# 02_-_Power_CSI_and_Bank_Power.net
KiCad netlist of a schematic drawn in Altium Designer
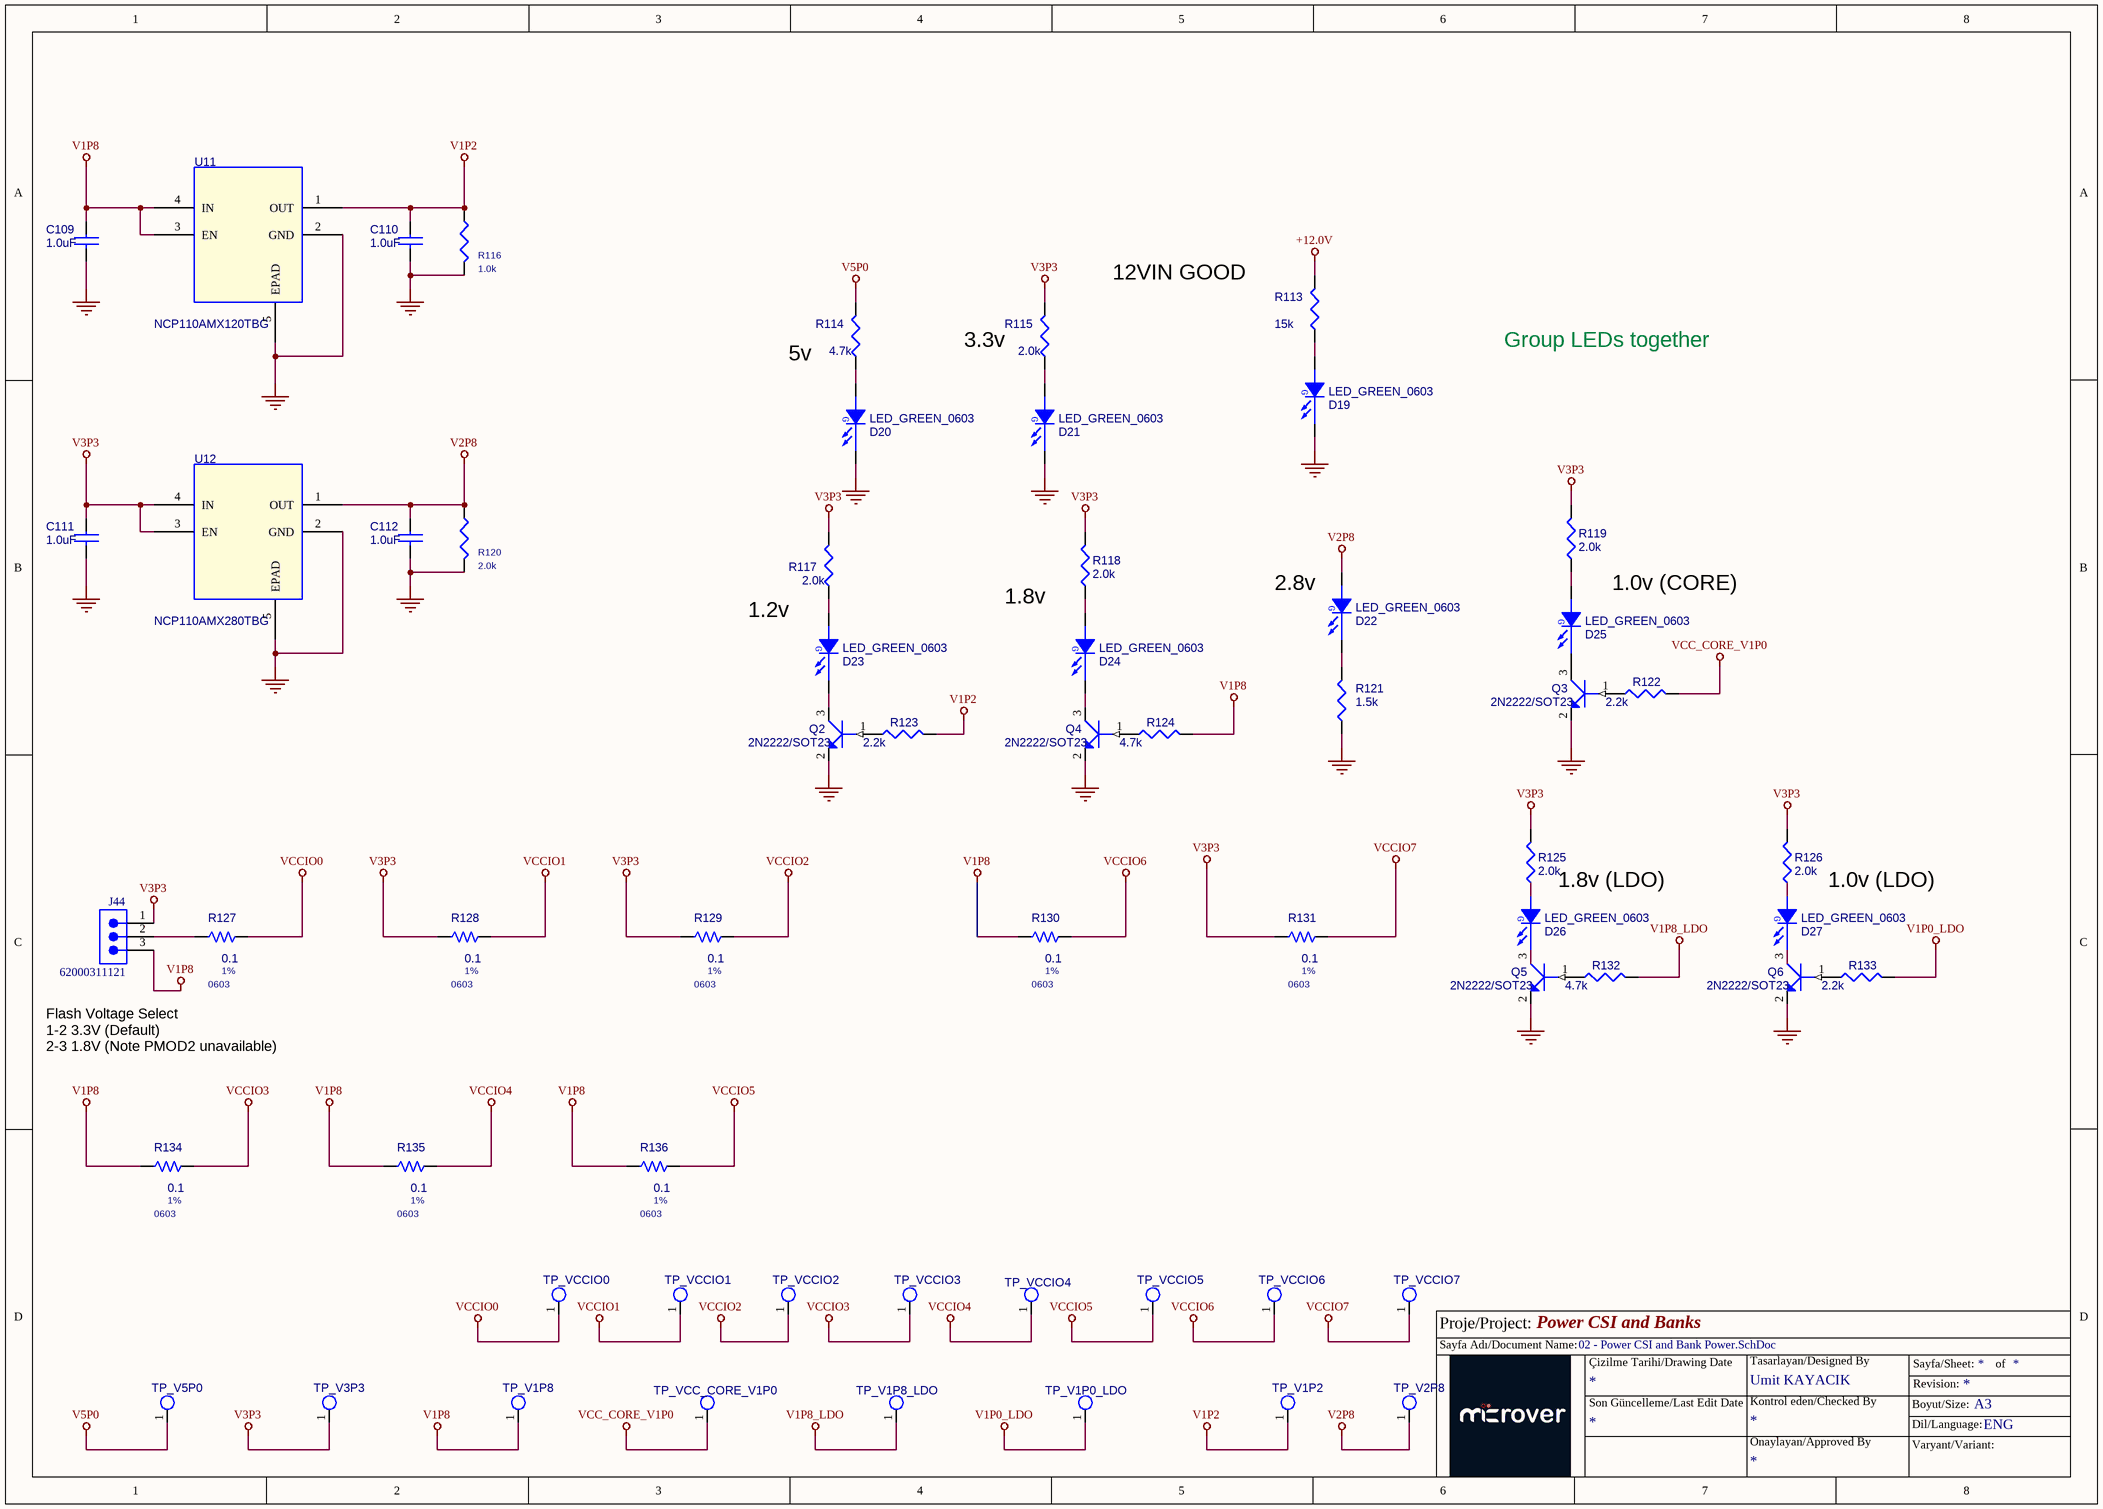
[diagram p0: 02 - Power CSI and Bank Power.SchDoc]

(export (version "E")
  (design (tool "Eeschema 10.0.6"))
  (components
    (comp (ref "C109")
      (value "1.0uF")
      (footprint "C0603")
      (description "CAP CER 10UF 10V 20% X6S 0603")
      (fields
        (field (name "MANUFACTURER PART NUMBER") "CL10X106MP8NRNC")
        (field (name "MANUFACTURER") "Samsung")
      )
      (libsource (lib "*") (part "CAP NP"))
    )
    (comp (ref "C110")
      (value "1.0uF")
      (footprint "C0603")
      (description "CAP CER 10UF 10V 20% X6S 0603")
      (fields
        (field (name "MANUFACTURER PART NUMBER") "CL10X106MP8NRNC")
        (field (name "MANUFACTURER") "Samsung")
      )
      (libsource (lib "*") (part "CAP NP"))
    )
    (comp (ref "C111")
      (value "1.0uF")
      (footprint "C0603")
      (description "CAP CER 10UF 10V 20% X6S 0603")
      (fields (field (name "MFG") "Samsung") (field (name "MAN. PART #") "CL10X106MP8NRNC"))
      (libsource (lib "*") (part "CAP NP"))
    )
    (comp (ref "C112")
      (value "1.0uF")
      (footprint "C0603")
      (description "CAP CER 10UF 10V 20% X6S 0603")
      (fields (field (name "MFG") "Samsung") (field (name "MAN. PART #") "CL10X106MP8NRNC"))
      (libsource (lib "*") (part "CAP NP"))
    )
    (comp (ref "D19")
      (value "LED_GREEN_0603")
      (footprint "APT1608")
      (libsource (lib "*") (part "LED-SMT1206_GREEN_1"))
    )
    (comp (ref "D20")
      (value "LED_GREEN_0603")
      (footprint "APT1608")
      (libsource (lib "*") (part "LED-SMT1206_GREEN_1"))
    )
    (comp (ref "D21")
      (value "LED_GREEN_0603")
      (footprint "APT1608")
      (libsource (lib "*") (part "LED-SMT1206_GREEN_1"))
    )
    (comp (ref "D22")
      (value "LED_GREEN_0603")
      (footprint "APT1608")
      (libsource (lib "*") (part "LED-SMT1206_GREEN_1"))
    )
    (comp (ref "D23")
      (value "LED_GREEN_0603")
      (footprint "APT1608")
      (libsource (lib "*") (part "LED-SMT1206_GREEN_1"))
    )
    (comp (ref "D24")
      (value "LED_GREEN_0603")
      (footprint "APT1608")
      (libsource (lib "*") (part "LED-SMT1206_GREEN_1"))
    )
    (comp (ref "D25")
      (value "LED_GREEN_0603")
      (footprint "APT1608")
      (libsource (lib "*") (part "LED-SMT1206_GREEN_1"))
    )
    (comp (ref "D26")
      (value "LED_GREEN_0603")
      (footprint "APT1608")
      (libsource (lib "*") (part "LED-SMT1206_GREEN_1"))
    )
    (comp (ref "D27")
      (value "LED_GREEN_0603")
      (footprint "APT1608")
      (libsource (lib "*") (part "LED-SMT1206_GREEN_1"))
    )
    (comp (ref "J44")
      (value "62000311121")
      (footprint "62000311121")
      (description "THT Vertical Pin Header WR-PHD, Pitch 2.00 mm, Single Row, 3 pins")
      (libsource (lib "Altium Content Vault") (part "Header_Male_1R_03P"))
    )
    (comp (ref "Q2") (value "2N2222/SOT23") (footprint "MMBT2222ALT-1") (libsource (lib "*") (part "2N2222")))
    (comp (ref "Q3") (value "2N2222/SOT23") (footprint "MMBT2222ALT-1") (libsource (lib "*") (part "2N2222")))
    (comp (ref "Q4") (value "2N2222/SOT23") (footprint "MMBT2222ALT-1") (libsource (lib "*") (part "2N2222")))
    (comp (ref "Q5") (value "2N2222/SOT23") (footprint "MMBT2222ALT-1") (libsource (lib "*") (part "2N2222")))
    (comp (ref "Q6") (value "2N2222/SOT23") (footprint "MMBT2222ALT-1") (libsource (lib "*") (part "2N2222")))
    (comp (ref "R113") (value "15k") (footprint "RLP-103") (libsource (lib "*") (part "RES_0")))
    (comp (ref "R114")
      (value "4.7k")
      (footprint "R0402")
      (description "RES SMD 2.2K OHM 1% 1/10W 0402")
      (fields
        (field (name "MANUFACTURER PART NUMBER") "ERJ-2RKF2201X")
        (field (name "MANUFACTURER") "Panasonic")
      )
      (libsource (lib "*") (part "RES_0"))
    )
    (comp (ref "R115")
      (value "2.0k")
      (footprint "R0402")
      (description "RES SMD 1K OHM 1% 1/10W 0402")
      (fields
        (field (name "MANUFACTURER") "Panasonic")
        (field (name "MANUFACTURER PART NUMBER") "ERJ-2RKF1001X")
      )
      (libsource (lib "*") (part "RES_0"))
    )
    (comp (ref "R116")
      (value "1.0k")
      (footprint "R0402")
      (description "RES SMD 1K OHM 1% 1/10W 0402")
      (fields (field (name "MFG") "Stackpole Electronics Inc") (field (name "MANUFACTURER") "Panasonic"))
      (libsource (lib "*") (part "RES_1K_1W16_0402_5P"))
    )
    (comp (ref "R117")
      (value "2.0k")
      (footprint "R0402")
      (description "RES SMD 1K OHM 1% 1/10W 0402")
      (fields
        (field (name "MANUFACTURER PART NUMBER") "ERJ-2RKF1001X")
        (field (name "MANUFACTURER") "Panasonic")
      )
      (libsource (lib "*") (part "RES_0"))
    )
    (comp (ref "R118")
      (value "2.0k")
      (footprint "R0402")
      (description "RES SMD 1K OHM 1% 1/10W 0402")
      (fields
        (field (name "MANUFACTURER PART NUMBER") "ERJ-2RKF1001X")
        (field (name "MANUFACTURER") "Panasonic")
      )
      (libsource (lib "*") (part "RES_0"))
    )
    (comp (ref "R119")
      (value "2.0k")
      (footprint "R0402")
      (description "RES SMD 1K OHM 1% 1/10W 0402")
      (fields
        (field (name "MANUFACTURER PART NUMBER") "ERJ-2RKF1001X")
        (field (name "MANUFACTURER") "Panasonic")
      )
      (libsource (lib "*") (part "RES_0"))
    )
    (comp (ref "R120")
      (value "2.0k")
      (footprint "R0402")
      (description "RES SMD 1K OHM 1% 1/10W 0402")
      (fields
        (field (name "MFG") "Stackpole Electronics Inc")
        (field (name "MANUFACTURER PART NUMBER") "ERJ-2RKF1001X")
      )
      (libsource (lib "*") (part "RES_1K_1W16_0402_5P"))
    )
    (comp (ref "R121")
      (value "1.5k")
      (footprint "R0402")
      (description "RES SMD 750 OHM 5% 1/10W 0402")
      (fields
        (field (name "MANUFACTURER") "Panasonic")
        (field (name "MANUFACTURER PART NUMBER") "ERJ-2GEJ751X")
      )
      (libsource (lib "*") (part "RES_0"))
    )
    (comp (ref "R122")
      (value "2.2k")
      (footprint "R0402")
      (description "RES SMD 4.7K OHM 5% 1/10W 0402")
      (fields
        (field (name "MANUFACTURER") "Panasonic")
        (field (name "MANUFACTURER PART NUMBER") "ERJ-2GEJ472X")
      )
      (libsource (lib "*") (part "RES_0"))
    )
    (comp (ref "R123")
      (value "2.2k")
      (footprint "R0402")
      (description "RES SMD 4.7K OHM 5% 1/10W 0402")
      (fields
        (field (name "MANUFACTURER") "Panasonic")
        (field (name "MANUFACTURER PART NUMBER") "ERJ-2GEJ472X")
      )
      (libsource (lib "*") (part "RES_0"))
    )
    (comp (ref "R124")
      (value "4.7k")
      (footprint "R0402")
      (description "RES SMD 4.7K OHM 5% 1/10W 0402")
      (fields
        (field (name "MANUFACTURER") "Panasonic")
        (field (name "MANUFACTURER PART NUMBER") "ERJ-2GEJ472X")
      )
      (libsource (lib "*") (part "RES_0"))
    )
    (comp (ref "R125")
      (value "2.0k")
      (footprint "R0402")
      (description "RES SMD 1K OHM 1% 1/10W 0402")
      (fields
        (field (name "MANUFACTURER") "Panasonic")
        (field (name "MANUFACTURER PART NUMBER") "ERJ-2RKF1001X")
      )
      (libsource (lib "*") (part "RES_0"))
    )
    (comp (ref "R126")
      (value "2.0k")
      (footprint "R0402")
      (description "RES SMD 1K OHM 1% 1/10W 0402")
      (fields
        (field (name "MANUFACTURER PART NUMBER") "ERJ-2RKF1001X")
        (field (name "MANUFACTURER") "Panasonic")
      )
      (libsource (lib "*") (part "RES_0"))
    )
    (comp (ref "R127")
      (value "0.1")
      (footprint "0603")
      (fields
        (field (name "VOLTAGE") "RVMAX")
        (field (name "POWER") "RMAX")
        (field (name "TOLLERANCE") "1%")
        (field (name "PCB FOOTPRINT") "0603")
      )
      (libsource (lib "*") (part "R_Dup2"))
    )
    (comp (ref "R128")
      (value "0.1")
      (footprint "0603")
      (fields
        (field (name "VOLTAGE") "RVMAX")
        (field (name "POWER") "RMAX")
        (field (name "TOLLERANCE") "1%")
        (field (name "PCB FOOTPRINT") "0603")
      )
      (libsource (lib "*") (part "R_Dup2"))
    )
    (comp (ref "R129")
      (value "0.1")
      (footprint "0603")
      (fields
        (field (name "VOLTAGE") "RVMAX")
        (field (name "POWER") "RMAX")
        (field (name "TOLLERANCE") "1%")
        (field (name "PCB FOOTPRINT") "0603")
      )
      (libsource (lib "*") (part "R_Dup2"))
    )
    (comp (ref "R130")
      (value "0.1")
      (footprint "0603")
      (fields
        (field (name "VOLTAGE") "RVMAX")
        (field (name "POWER") "RMAX")
        (field (name "TOLLERANCE") "1%")
        (field (name "PCB FOOTPRINT") "0603")
      )
      (libsource (lib "*") (part "R_Dup2"))
    )
    (comp (ref "R131")
      (value "0.1")
      (footprint "0603")
      (fields
        (field (name "VOLTAGE") "RVMAX")
        (field (name "POWER") "RMAX")
        (field (name "TOLLERANCE") "1%")
        (field (name "PCB FOOTPRINT") "0603")
      )
      (libsource (lib "*") (part "R_Dup2"))
    )
    (comp (ref "R132")
      (value "4.7k")
      (footprint "R0402")
      (description "RES SMD 4.7K OHM 5% 1/10W 0402")
      (fields (field (name "MANUFACTURER PART NUMBER") "ERJ-2GEJ472X") (field (name "MFG") "Panasonic"))
      (libsource (lib "*") (part "RES_0"))
    )
    (comp (ref "R133")
      (value "2.2k")
      (footprint "R0402")
      (description "RES SMD 4.7K OHM 5% 1/10W 0402")
      (fields (field (name "MANUFACTURER PART NUMBER") "ERJ-2GEJ472X") (field (name "MFG") "Panasonic"))
      (libsource (lib "*") (part "RES_0"))
    )
    (comp (ref "R134")
      (value "0.1")
      (footprint "0603")
      (fields
        (field (name "VOLTAGE") "RVMAX")
        (field (name "POWER") "RMAX")
        (field (name "TOLLERANCE") "1%")
        (field (name "PCB FOOTPRINT") "0603")
      )
      (libsource (lib "*") (part "R_Dup2"))
    )
    (comp (ref "R135")
      (value "0.1")
      (footprint "0603")
      (fields
        (field (name "VOLTAGE") "RVMAX")
        (field (name "POWER") "RMAX")
        (field (name "TOLLERANCE") "1%")
        (field (name "PCB FOOTPRINT") "0603")
      )
      (libsource (lib "*") (part "R_Dup2"))
    )
    (comp (ref "R136")
      (value "0.1")
      (footprint "0603")
      (fields
        (field (name "VOLTAGE") "RVMAX")
        (field (name "POWER") "RMAX")
        (field (name "TOLLERANCE") "1%")
        (field (name "PCB FOOTPRINT") "0603")
      )
      (libsource (lib "*") (part "R_Dup2"))
    )
    (comp (ref "TP_V1P0_LDO")
      (value "TP_S_40_63")
      (footprint "TP_1MM")
      (description "Square test point, 40mil inner diameter, 63mil outer diameter")
      (libsource (lib "*") (part "TP_S_40_63"))
    )
    (comp (ref "TP_V1P2")
      (value "TP_S_40_63")
      (footprint "TP_1MM")
      (description "Square test point, 40mil inner diameter, 63mil outer diameter")
      (libsource (lib "*") (part "TP_S_40_63"))
    )
    (comp (ref "TP_V1P8")
      (value "TP_S_40_63")
      (footprint "TP_1MM")
      (description "Square test point, 40mil inner diameter, 63mil outer diameter")
      (libsource (lib "*") (part "TP_S_40_63"))
    )
    (comp (ref "TP_V1P8_LDO")
      (value "TP_S_40_63")
      (footprint "TP_1MM")
      (description "Square test point, 40mil inner diameter, 63mil outer diameter")
      (libsource (lib "*") (part "TP_S_40_63"))
    )
    (comp (ref "TP_V2P8")
      (value "TP_S_40_63")
      (footprint "TP_1MM")
      (description "Square test point, 40mil inner diameter, 63mil outer diameter")
      (libsource (lib "*") (part "TP_S_40_63"))
    )
    (comp (ref "TP_V3P3")
      (value "TP_S_40_63")
      (footprint "TP_1MM")
      (description "Square test point, 40mil inner diameter, 63mil outer diameter")
      (libsource (lib "*") (part "TP_S_40_63"))
    )
    (comp (ref "TP_V5P0")
      (value "TP_S_40_63")
      (footprint "TP_1MM")
      (description "Square test point, 40mil inner diameter, 63mil outer diameter")
      (libsource (lib "*") (part "TP_S_40_63"))
    )
    (comp (ref "TP_VCCIO0")
      (value "TP_S_40_63")
      (footprint "TP_1MM")
      (description "Square test point, 40mil inner diameter, 63mil outer diameter")
      (libsource (lib "*") (part "TP_S_40_63"))
    )
    (comp (ref "TP_VCCIO1")
      (value "TP_S_40_63")
      (footprint "TP_1MM")
      (description "Square test point, 40mil inner diameter, 63mil outer diameter")
      (libsource (lib "*") (part "TP_S_40_63"))
    )
    (comp (ref "TP_VCCIO2")
      (value "TP_S_40_63")
      (footprint "TP_1MM")
      (description "Square test point, 40mil inner diameter, 63mil outer diameter")
      (libsource (lib "*") (part "TP_S_40_63"))
    )
    (comp (ref "TP_VCCIO3")
      (value "TP_S_40_63")
      (footprint "TP_1MM")
      (description "Square test point, 40mil inner diameter, 63mil outer diameter")
      (libsource (lib "*") (part "TP_S_40_63"))
    )
    (comp (ref "TP_VCCIO4")
      (value "TP_S_40_63")
      (footprint "TP_1MM")
      (description "Square test point, 40mil inner diameter, 63mil outer diameter")
      (libsource (lib "*") (part "TP_S_40_63"))
    )
    (comp (ref "TP_VCCIO5")
      (value "TP_S_40_63")
      (footprint "TP_1MM")
      (description "Square test point, 40mil inner diameter, 63mil outer diameter")
      (libsource (lib "*") (part "TP_S_40_63"))
    )
    (comp (ref "TP_VCCIO6")
      (value "TP_S_40_63")
      (footprint "TP_1MM")
      (description "Square test point, 40mil inner diameter, 63mil outer diameter")
      (libsource (lib "*") (part "TP_S_40_63"))
    )
    (comp (ref "TP_VCCIO7")
      (value "TP_S_40_63")
      (footprint "TP_1MM")
      (description "Square test point, 40mil inner diameter, 63mil outer diameter")
      (libsource (lib "*") (part "TP_S_40_63"))
    )
    (comp (ref "TP_VCC_CORE_V1P0")
      (value "TP_S_40_63")
      (footprint "TP_1MM")
      (description "Square test point, 40mil inner diameter, 63mil outer diameter")
      (libsource (lib "*") (part "TP_S_40_63"))
    )
    (comp (ref "U11")
      (value "NCP110AMX120TBG")
      (footprint "4XDFN_NCP110")
      (libsource (lib "*") (part "NCP110AMX120TBG"))
    )
    (comp (ref "U12")
      (value "NCP110AMX280TBG")
      (footprint "4XDFN_NCP110")
      (libsource (lib "*") (part "NCP110AMX280TBG"))
    )
  )
  (nets
    (net (code "1") (name "+12.0V") (class "Default")
      (node (ref "R113") (pin "2") (pinfunction "2_2") (pintype "passive"))
    )
    (net (code "2") (name "GND") (class "Default")
      (node (ref "C109") (pin "2") (pinfunction "2_2") (pintype "passive"))
      (node (ref "C110") (pin "2") (pinfunction "2_2") (pintype "passive"))
      (node (ref "C111") (pin "2") (pinfunction "2_2") (pintype "passive"))
      (node (ref "C112") (pin "2") (pinfunction "2_2") (pintype "passive"))
      (node (ref "D19") (pin "1") (pinfunction "CATHODE_1") (pintype "passive"))
      (node (ref "D20") (pin "1") (pinfunction "CATHODE_1") (pintype "passive"))
      (node (ref "D21") (pin "1") (pinfunction "CATHODE_1") (pintype "passive"))
      (node (ref "Q2") (pin "2") (pinfunction "EMITTER_2") (pintype "passive"))
      (node (ref "Q3") (pin "2") (pinfunction "EMITTER_2") (pintype "passive"))
      (node (ref "Q4") (pin "2") (pinfunction "EMITTER_2") (pintype "passive"))
      (node (ref "Q5") (pin "2") (pinfunction "EMITTER_2") (pintype "passive"))
      (node (ref "Q6") (pin "2") (pinfunction "EMITTER_2") (pintype "passive"))
      (node (ref "R116") (pin "2") (pinfunction "2_2") (pintype "passive"))
      (node (ref "R120") (pin "2") (pinfunction "2_2") (pintype "passive"))
      (node (ref "R121") (pin "1") (pinfunction "1_1") (pintype "passive"))
      (node (ref "U11") (pin "2") (pinfunction "GND_2") (pintype "passive"))
      (node (ref "U11") (pin "5") (pinfunction "EPAD_5") (pintype "passive"))
      (node (ref "U12") (pin "2") (pinfunction "GND_2") (pintype "passive"))
      (node (ref "U12") (pin "5") (pinfunction "EPAD_5") (pintype "passive"))
    )
    (net (code "3") (name "Net-(D19-ANODE)") (class "Default")
      (node (ref "D19") (pin "2") (pinfunction "ANODE_2") (pintype "passive"))
      (node (ref "R113") (pin "1") (pinfunction "1_1") (pintype "passive"))
    )
    (net (code "4") (name "Net-(D20-ANODE)") (class "Default")
      (node (ref "D20") (pin "2") (pinfunction "ANODE_2") (pintype "passive"))
      (node (ref "R114") (pin "1") (pinfunction "1_1") (pintype "passive"))
    )
    (net (code "5") (name "Net-(D21-ANODE)") (class "Default")
      (node (ref "D21") (pin "2") (pinfunction "ANODE_2") (pintype "passive"))
      (node (ref "R115") (pin "1") (pinfunction "1_1") (pintype "passive"))
    )
    (net (code "6") (name "Net-(D22-CATHODE)") (class "Default")
      (node (ref "D22") (pin "1") (pinfunction "CATHODE_1") (pintype "passive"))
      (node (ref "R121") (pin "2") (pinfunction "2_2") (pintype "passive"))
    )
    (net (code "7") (name "Net-(D23-ANODE)") (class "Default")
      (node (ref "D23") (pin "2") (pinfunction "ANODE_2") (pintype "passive"))
      (node (ref "R117") (pin "1") (pinfunction "1_1") (pintype "passive"))
    )
    (net (code "8") (name "Net-(D23-CATHODE)") (class "Default")
      (node (ref "D23") (pin "1") (pinfunction "CATHODE_1") (pintype "passive"))
      (node (ref "Q2") (pin "3") (pinfunction "COLLECTOR_3") (pintype "passive"))
    )
    (net (code "9") (name "Net-(D24-ANODE)") (class "Default")
      (node (ref "D24") (pin "2") (pinfunction "ANODE_2") (pintype "passive"))
      (node (ref "R118") (pin "1") (pinfunction "1_1") (pintype "passive"))
    )
    (net (code "10") (name "Net-(D24-CATHODE)") (class "Default")
      (node (ref "D24") (pin "1") (pinfunction "CATHODE_1") (pintype "passive"))
      (node (ref "Q4") (pin "3") (pinfunction "COLLECTOR_3") (pintype "passive"))
    )
    (net (code "11") (name "Net-(D25-ANODE)") (class "Default")
      (node (ref "D25") (pin "2") (pinfunction "ANODE_2") (pintype "passive"))
      (node (ref "R119") (pin "1") (pinfunction "1_1") (pintype "passive"))
    )
    (net (code "12") (name "Net-(D25-CATHODE)") (class "Default")
      (node (ref "D25") (pin "1") (pinfunction "CATHODE_1") (pintype "passive"))
      (node (ref "Q3") (pin "3") (pinfunction "COLLECTOR_3") (pintype "passive"))
    )
    (net (code "13") (name "Net-(D26-ANODE)") (class "Default")
      (node (ref "D26") (pin "2") (pinfunction "ANODE_2") (pintype "passive"))
      (node (ref "R125") (pin "1") (pinfunction "1_1") (pintype "passive"))
    )
    (net (code "14") (name "Net-(D26-CATHODE)") (class "Default")
      (node (ref "D26") (pin "1") (pinfunction "CATHODE_1") (pintype "passive"))
      (node (ref "Q5") (pin "3") (pinfunction "COLLECTOR_3") (pintype "passive"))
    )
    (net (code "15") (name "Net-(D27-ANODE)") (class "Default")
      (node (ref "D27") (pin "2") (pinfunction "ANODE_2") (pintype "passive"))
      (node (ref "R126") (pin "1") (pinfunction "1_1") (pintype "passive"))
    )
    (net (code "16") (name "Net-(D27-CATHODE)") (class "Default")
      (node (ref "D27") (pin "1") (pinfunction "CATHODE_1") (pintype "passive"))
      (node (ref "Q6") (pin "3") (pinfunction "COLLECTOR_3") (pintype "passive"))
    )
    (net (code "17") (name "Net-(J44-Pad2)") (class "Default")
      (node (ref "J44") (pin "2") (pinfunction "2_2") (pintype "passive"))
      (node (ref "R127") (pin "1") (pinfunction "1_1") (pintype "passive"))
    )
    (net (code "18") (name "Net-(Q2-BASE)") (class "Default")
      (node (ref "Q2") (pin "1") (pinfunction "BASE_1") (pintype "input"))
      (node (ref "R123") (pin "1") (pinfunction "1_1") (pintype "passive"))
    )
    (net (code "19") (name "Net-(Q3-BASE)") (class "Default")
      (node (ref "Q3") (pin "1") (pinfunction "BASE_1") (pintype "input"))
      (node (ref "R122") (pin "1") (pinfunction "1_1") (pintype "passive"))
    )
    (net (code "20") (name "Net-(Q4-BASE)") (class "Default")
      (node (ref "Q4") (pin "1") (pinfunction "BASE_1") (pintype "input"))
      (node (ref "R124") (pin "1") (pinfunction "1_1") (pintype "passive"))
    )
    (net (code "21") (name "Net-(Q5-BASE)") (class "Default")
      (node (ref "Q5") (pin "1") (pinfunction "BASE_1") (pintype "input"))
      (node (ref "R132") (pin "1") (pinfunction "1_1") (pintype "passive"))
    )
    (net (code "22") (name "Net-(Q6-BASE)") (class "Default")
      (node (ref "Q6") (pin "1") (pinfunction "BASE_1") (pintype "input"))
      (node (ref "R133") (pin "1") (pinfunction "1_1") (pintype "passive"))
    )
    (net (code "23") (name "V1P0_LDO") (class "Default")
      (node (ref "R133") (pin "2") (pinfunction "2_2") (pintype "passive"))
      (node (ref "TP_V1P0_LDO") (pin "1") (pinfunction "TP_1") (pintype "passive"))
    )
    (net (code "24") (name "V1P2") (class "Default")
      (node (ref "C110") (pin "1") (pinfunction "1_1") (pintype "passive"))
      (node (ref "R116") (pin "1") (pinfunction "1_1") (pintype "passive"))
      (node (ref "R123") (pin "2") (pinfunction "2_2") (pintype "passive"))
      (node (ref "TP_V1P2") (pin "1") (pinfunction "TP_1") (pintype "passive"))
      (node (ref "U11") (pin "1") (pinfunction "OUT_1") (pintype "passive"))
    )
    (net (code "25") (name "V1P8") (class "Default")
      (node (ref "C109") (pin "1") (pinfunction "1_1") (pintype "passive"))
      (node (ref "J44") (pin "3") (pinfunction "3_3") (pintype "passive"))
      (node (ref "R124") (pin "2") (pinfunction "2_2") (pintype "passive"))
      (node (ref "R130") (pin "1") (pinfunction "1_1") (pintype "passive"))
      (node (ref "R134") (pin "1") (pinfunction "1_1") (pintype "passive"))
      (node (ref "R135") (pin "1") (pinfunction "1_1") (pintype "passive"))
      (node (ref "R136") (pin "1") (pinfunction "1_1") (pintype "passive"))
      (node (ref "TP_V1P8") (pin "1") (pinfunction "TP_1") (pintype "passive"))
      (node (ref "U11") (pin "3") (pinfunction "EN_3") (pintype "passive"))
      (node (ref "U11") (pin "4") (pinfunction "IN_4") (pintype "passive"))
    )
    (net (code "26") (name "V1P8_LDO") (class "Default")
      (node (ref "R132") (pin "2") (pinfunction "2_2") (pintype "passive"))
      (node (ref "TP_V1P8_LDO") (pin "1") (pinfunction "TP_1") (pintype "passive"))
    )
    (net (code "27") (name "V2P8") (class "Default")
      (node (ref "C112") (pin "1") (pinfunction "1_1") (pintype "passive"))
      (node (ref "D22") (pin "2") (pinfunction "ANODE_2") (pintype "passive"))
      (node (ref "R120") (pin "1") (pinfunction "1_1") (pintype "passive"))
      (node (ref "TP_V2P8") (pin "1") (pinfunction "TP_1") (pintype "passive"))
      (node (ref "U12") (pin "1") (pinfunction "OUT_1") (pintype "passive"))
    )
    (net (code "28") (name "V3P3") (class "Default")
      (node (ref "C111") (pin "1") (pinfunction "1_1") (pintype "passive"))
      (node (ref "J44") (pin "1") (pinfunction "1_1") (pintype "passive"))
      (node (ref "R115") (pin "2") (pinfunction "2_2") (pintype "passive"))
      (node (ref "R117") (pin "2") (pinfunction "2_2") (pintype "passive"))
      (node (ref "R118") (pin "2") (pinfunction "2_2") (pintype "passive"))
      (node (ref "R119") (pin "2") (pinfunction "2_2") (pintype "passive"))
      (node (ref "R125") (pin "2") (pinfunction "2_2") (pintype "passive"))
      (node (ref "R126") (pin "2") (pinfunction "2_2") (pintype "passive"))
      (node (ref "R128") (pin "1") (pinfunction "1_1") (pintype "passive"))
      (node (ref "R129") (pin "1") (pinfunction "1_1") (pintype "passive"))
      (node (ref "R131") (pin "1") (pinfunction "1_1") (pintype "passive"))
      (node (ref "TP_V3P3") (pin "1") (pinfunction "TP_1") (pintype "passive"))
      (node (ref "U12") (pin "3") (pinfunction "EN_3") (pintype "passive"))
      (node (ref "U12") (pin "4") (pinfunction "IN_4") (pintype "passive"))
    )
    (net (code "29") (name "V5P0") (class "Default")
      (node (ref "R114") (pin "2") (pinfunction "2_2") (pintype "passive"))
      (node (ref "TP_V5P0") (pin "1") (pinfunction "TP_1") (pintype "passive"))
    )
    (net (code "30") (name "VCCIO0") (class "Default")
      (node (ref "R127") (pin "2") (pinfunction "2_2") (pintype "passive"))
      (node (ref "TP_VCCIO0") (pin "1") (pinfunction "TP_1") (pintype "passive"))
    )
    (net (code "31") (name "VCCIO1") (class "Default")
      (node (ref "R128") (pin "2") (pinfunction "2_2") (pintype "passive"))
      (node (ref "TP_VCCIO1") (pin "1") (pinfunction "TP_1") (pintype "passive"))
    )
    (net (code "32") (name "VCCIO2") (class "Default")
      (node (ref "R129") (pin "2") (pinfunction "2_2") (pintype "passive"))
      (node (ref "TP_VCCIO2") (pin "1") (pinfunction "TP_1") (pintype "passive"))
    )
    (net (code "33") (name "VCCIO3") (class "Default")
      (node (ref "R134") (pin "2") (pinfunction "2_2") (pintype "passive"))
      (node (ref "TP_VCCIO3") (pin "1") (pinfunction "TP_1") (pintype "passive"))
    )
    (net (code "34") (name "VCCIO4") (class "Default")
      (node (ref "R135") (pin "2") (pinfunction "2_2") (pintype "passive"))
      (node (ref "TP_VCCIO4") (pin "1") (pinfunction "TP_1") (pintype "passive"))
    )
    (net (code "35") (name "VCCIO5") (class "Default")
      (node (ref "R136") (pin "2") (pinfunction "2_2") (pintype "passive"))
      (node (ref "TP_VCCIO5") (pin "1") (pinfunction "TP_1") (pintype "passive"))
    )
    (net (code "36") (name "VCCIO6") (class "Default")
      (node (ref "R130") (pin "2") (pinfunction "2_2") (pintype "passive"))
      (node (ref "TP_VCCIO6") (pin "1") (pinfunction "TP_1") (pintype "passive"))
    )
    (net (code "37") (name "VCCIO7") (class "Default")
      (node (ref "R131") (pin "2") (pinfunction "2_2") (pintype "passive"))
      (node (ref "TP_VCCIO7") (pin "1") (pinfunction "TP_1") (pintype "passive"))
    )
    (net (code "38") (name "VCC_CORE_V1P0") (class "Default")
      (node (ref "R122") (pin "2") (pinfunction "2_2") (pintype "passive"))
      (node (ref "TP_VCC_CORE_V1P0") (pin "1") (pinfunction "TP_1") (pintype "passive"))
    )
  )
)
